# VRAM_SIMM_TC524258BJ_v1_0_Sch_EasyEDA.net
KiCad netlist of a schematic drawn in EasyEDA
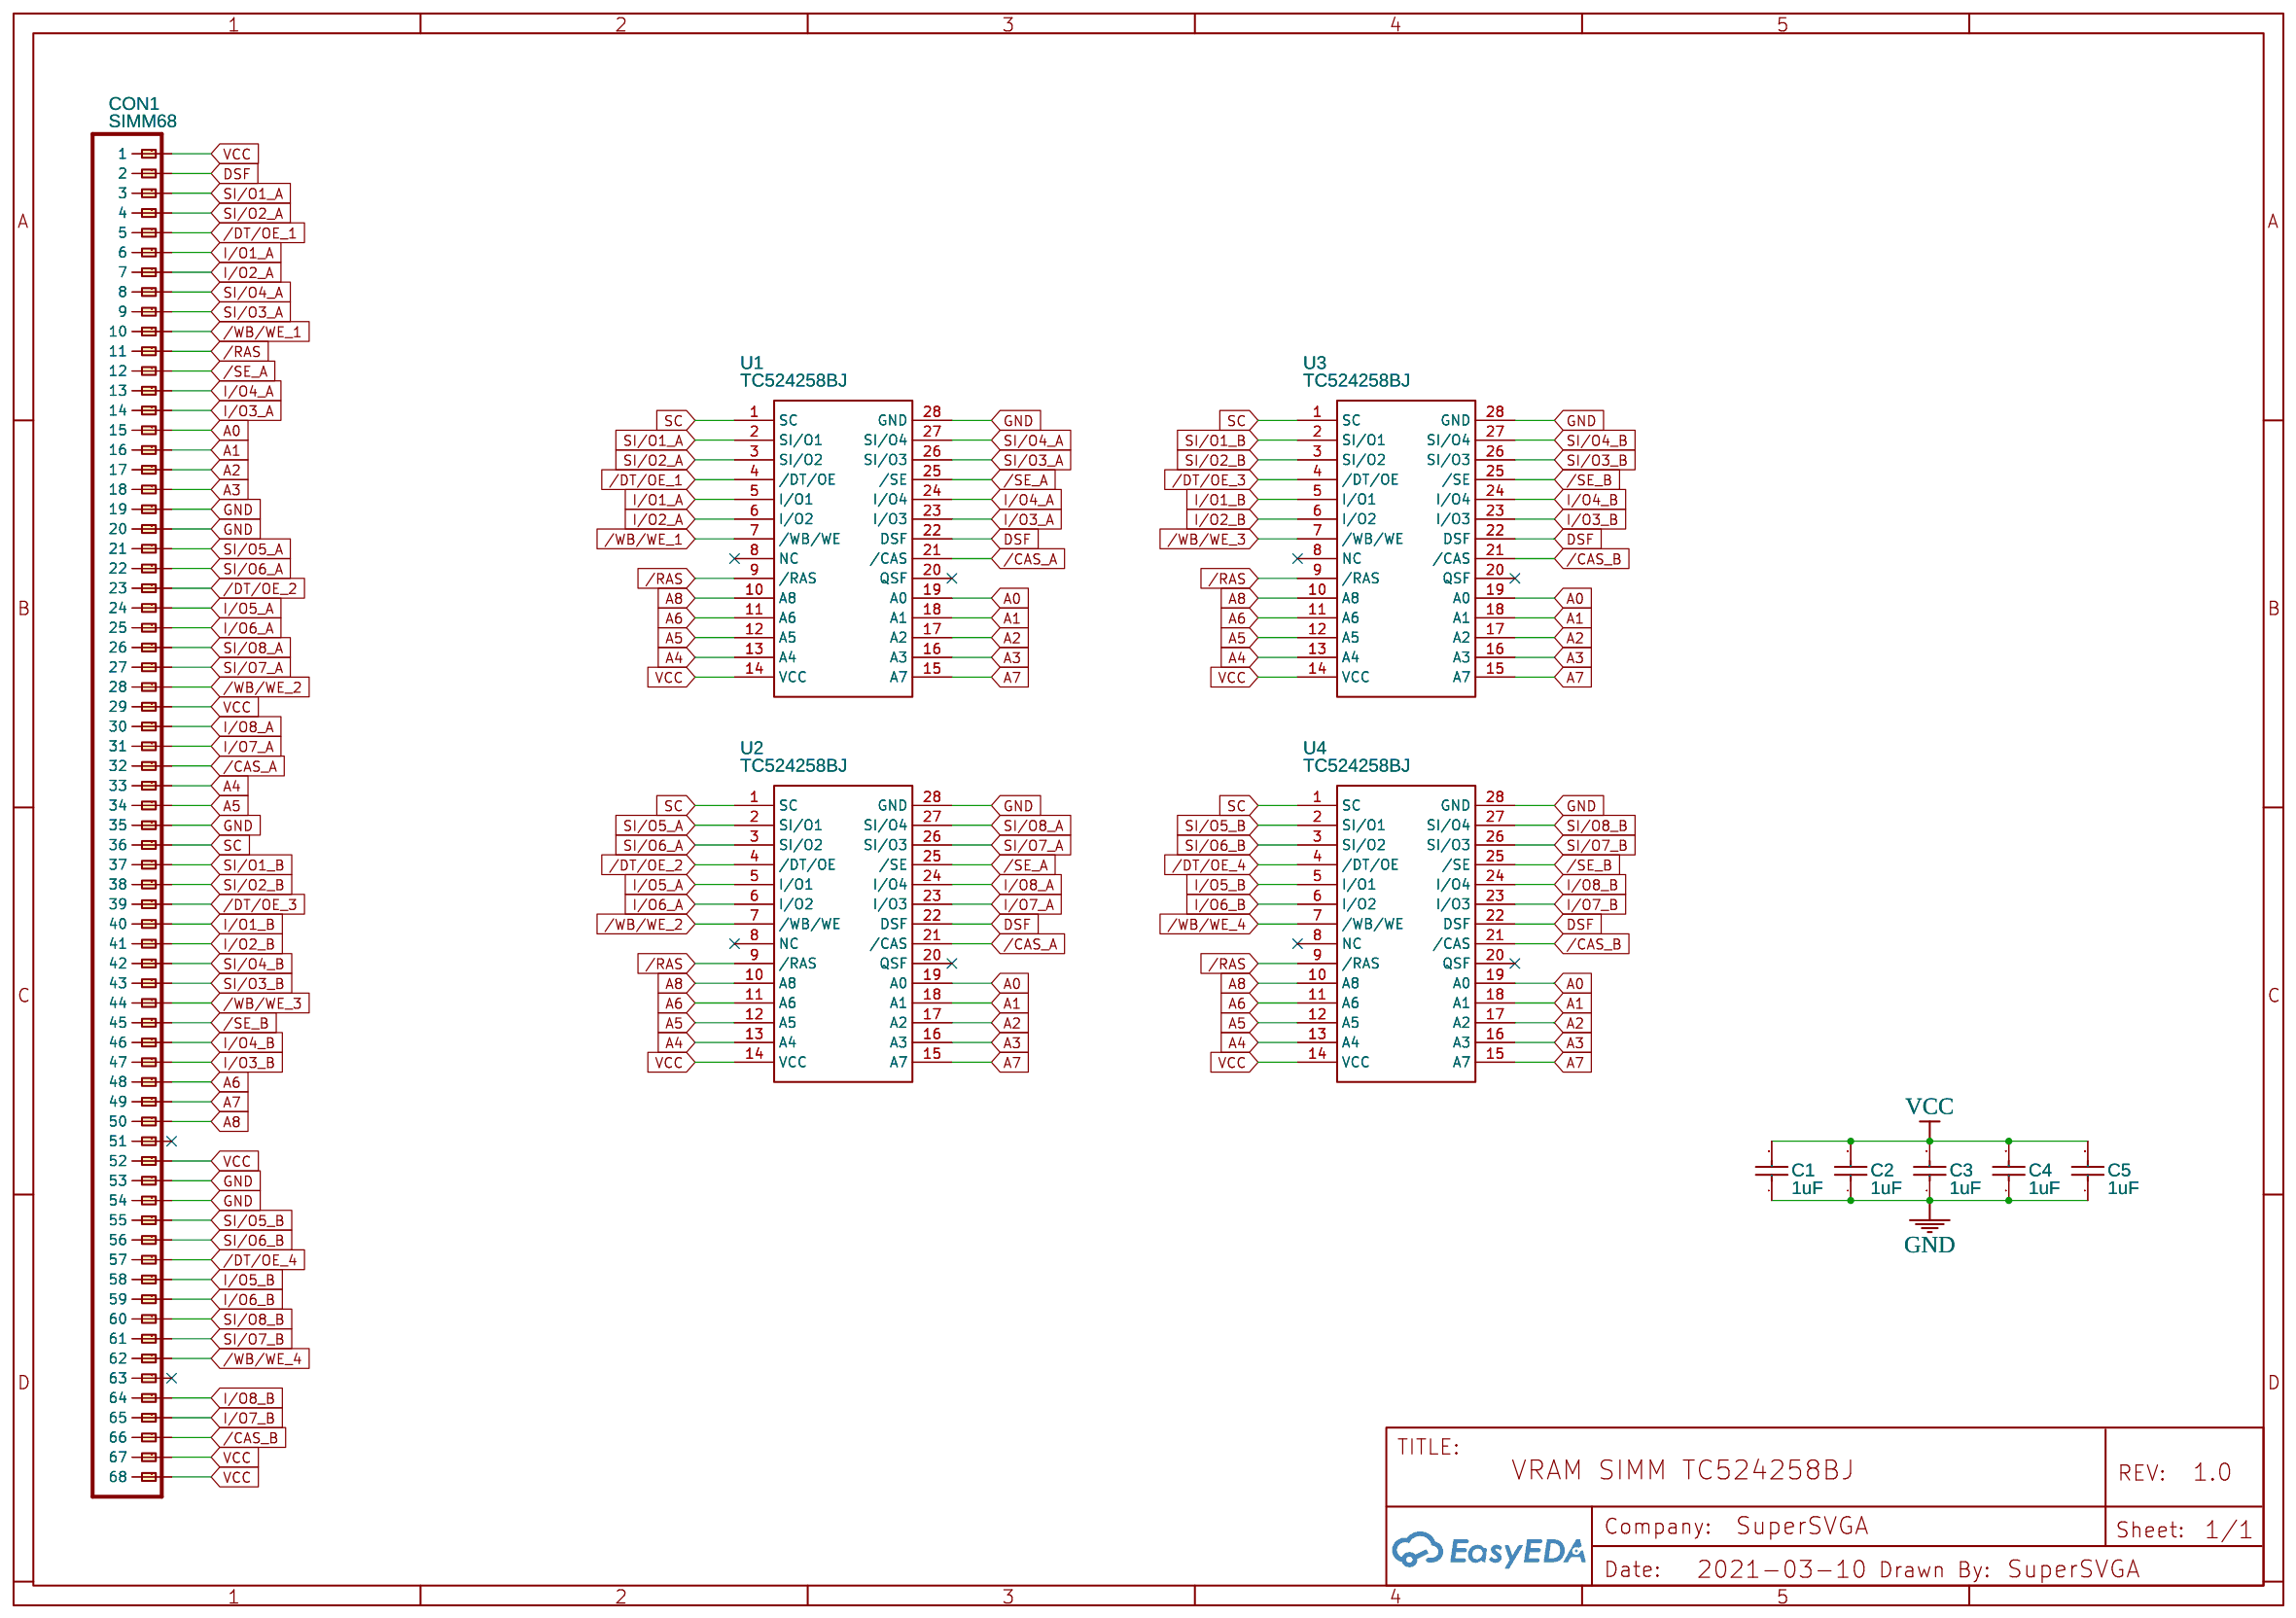
[diagram p0: schematic sheet]

(export (version "E")
  (design (tool "Eeschema 10.0.6"))
  (components
    (comp (ref "C1")
      (value "1uF")
      (fields
        (field (name "BOM_Manufacturer Part") "CL10A105KP8NNNC")
        (field (name "BOM_Supplier Part") "C26413")
      )
      (libsource (lib "") (part "CL10A105KP8NNNC"))
    )
    (comp (ref "C2")
      (value "1uF")
      (fields
        (field (name "BOM_Manufacturer Part") "CL10A105KP8NNNC")
        (field (name "BOM_Supplier Part") "C26413")
      )
      (libsource (lib "") (part "CL10A105KP8NNNC"))
    )
    (comp (ref "C3")
      (value "1uF")
      (fields
        (field (name "BOM_Manufacturer Part") "CL10A105KP8NNNC")
        (field (name "BOM_Supplier Part") "C26413")
      )
      (libsource (lib "") (part "CL10A105KP8NNNC"))
    )
    (comp (ref "C4")
      (value "1uF")
      (fields
        (field (name "BOM_Manufacturer Part") "CL10A105KP8NNNC")
        (field (name "BOM_Supplier Part") "C26413")
      )
      (libsource (lib "") (part "CL10A105KP8NNNC"))
    )
    (comp (ref "C5")
      (value "1uF")
      (fields
        (field (name "BOM_Manufacturer Part") "CL10A105KP8NNNC")
        (field (name "BOM_Supplier Part") "C26413")
      )
      (libsource (lib "") (part "CL10A105KP8NNNC"))
    )
    (comp (ref "CON1") (value "SIMM68") (libsource (lib "") (part "SIMM68")))
    (comp (ref "U1") (value "TC524258BJ") (libsource (lib "") (part "TC524258BJ")))
    (comp (ref "U2") (value "TC524258BJ") (libsource (lib "") (part "TC524258BJ")))
    (comp (ref "U3") (value "TC524258BJ") (libsource (lib "") (part "TC524258BJ")))
    (comp (ref "U4") (value "TC524258BJ") (libsource (lib "") (part "TC524258BJ")))
  )
  (nets
    (net (code "1") (name "A0") (class "Default")
      (node (ref "CON1") (pin "15") (pinfunction "15_15") (pintype "unspecified"))
      (node (ref "U1") (pin "19") (pinfunction "A0_19") (pintype "unspecified"))
      (node (ref "U2") (pin "19") (pinfunction "A0_19") (pintype "unspecified"))
      (node (ref "U3") (pin "19") (pinfunction "A0_19") (pintype "unspecified"))
      (node (ref "U4") (pin "19") (pinfunction "A0_19") (pintype "unspecified"))
    )
    (net (code "2") (name "A1") (class "Default")
      (node (ref "CON1") (pin "16") (pinfunction "16_16") (pintype "unspecified"))
      (node (ref "U1") (pin "18") (pinfunction "A1_18") (pintype "unspecified"))
      (node (ref "U2") (pin "18") (pinfunction "A1_18") (pintype "unspecified"))
      (node (ref "U3") (pin "18") (pinfunction "A1_18") (pintype "unspecified"))
      (node (ref "U4") (pin "18") (pinfunction "A1_18") (pintype "unspecified"))
    )
    (net (code "3") (name "A2") (class "Default")
      (node (ref "CON1") (pin "17") (pinfunction "17_17") (pintype "unspecified"))
      (node (ref "U1") (pin "17") (pinfunction "A2_17") (pintype "unspecified"))
      (node (ref "U2") (pin "17") (pinfunction "A2_17") (pintype "unspecified"))
      (node (ref "U3") (pin "17") (pinfunction "A2_17") (pintype "unspecified"))
      (node (ref "U4") (pin "17") (pinfunction "A2_17") (pintype "unspecified"))
    )
    (net (code "4") (name "A3") (class "Default")
      (node (ref "CON1") (pin "18") (pinfunction "18_18") (pintype "unspecified"))
      (node (ref "U1") (pin "16") (pinfunction "A3_16") (pintype "unspecified"))
      (node (ref "U2") (pin "16") (pinfunction "A3_16") (pintype "unspecified"))
      (node (ref "U3") (pin "16") (pinfunction "A3_16") (pintype "unspecified"))
      (node (ref "U4") (pin "16") (pinfunction "A3_16") (pintype "unspecified"))
    )
    (net (code "5") (name "A4") (class "Default")
      (node (ref "CON1") (pin "33") (pinfunction "33_33") (pintype "unspecified"))
      (node (ref "U1") (pin "13") (pinfunction "A4_13") (pintype "unspecified"))
      (node (ref "U2") (pin "13") (pinfunction "A4_13") (pintype "unspecified"))
      (node (ref "U3") (pin "13") (pinfunction "A4_13") (pintype "unspecified"))
      (node (ref "U4") (pin "13") (pinfunction "A4_13") (pintype "unspecified"))
    )
    (net (code "6") (name "A5") (class "Default")
      (node (ref "CON1") (pin "34") (pinfunction "34_34") (pintype "unspecified"))
      (node (ref "U1") (pin "12") (pinfunction "A5_12") (pintype "unspecified"))
      (node (ref "U2") (pin "12") (pinfunction "A5_12") (pintype "unspecified"))
      (node (ref "U3") (pin "12") (pinfunction "A5_12") (pintype "unspecified"))
      (node (ref "U4") (pin "12") (pinfunction "A5_12") (pintype "unspecified"))
    )
    (net (code "7") (name "A6") (class "Default")
      (node (ref "CON1") (pin "48") (pinfunction "48_48") (pintype "unspecified"))
      (node (ref "U1") (pin "11") (pinfunction "A6_11") (pintype "unspecified"))
      (node (ref "U2") (pin "11") (pinfunction "A6_11") (pintype "unspecified"))
      (node (ref "U3") (pin "11") (pinfunction "A6_11") (pintype "unspecified"))
      (node (ref "U4") (pin "11") (pinfunction "A6_11") (pintype "unspecified"))
    )
    (net (code "8") (name "A7") (class "Default")
      (node (ref "CON1") (pin "49") (pinfunction "49_49") (pintype "unspecified"))
      (node (ref "U1") (pin "15") (pinfunction "A7_15") (pintype "unspecified"))
      (node (ref "U2") (pin "15") (pinfunction "A7_15") (pintype "unspecified"))
      (node (ref "U3") (pin "15") (pinfunction "A7_15") (pintype "unspecified"))
      (node (ref "U4") (pin "15") (pinfunction "A7_15") (pintype "unspecified"))
    )
    (net (code "9") (name "A8") (class "Default")
      (node (ref "CON1") (pin "50") (pinfunction "50_50") (pintype "unspecified"))
      (node (ref "U1") (pin "10") (pinfunction "A8_10") (pintype "unspecified"))
      (node (ref "U2") (pin "10") (pinfunction "A8_10") (pintype "unspecified"))
      (node (ref "U3") (pin "10") (pinfunction "A8_10") (pintype "unspecified"))
      (node (ref "U4") (pin "10") (pinfunction "A8_10") (pintype "unspecified"))
    )
    (net (code "10") (name "DSF") (class "Default")
      (node (ref "CON1") (pin "2") (pinfunction "2_2") (pintype "unspecified"))
      (node (ref "U1") (pin "22") (pinfunction "DSF_22") (pintype "unspecified"))
      (node (ref "U2") (pin "22") (pinfunction "DSF_22") (pintype "unspecified"))
      (node (ref "U3") (pin "22") (pinfunction "DSF_22") (pintype "unspecified"))
      (node (ref "U4") (pin "22") (pinfunction "DSF_22") (pintype "unspecified"))
    )
    (net (code "11") (name "GND") (class "Default")
      (node (ref "C1") (pin "1") (pinfunction "1_1") (pintype "input"))
      (node (ref "C2") (pin "1") (pinfunction "1_1") (pintype "input"))
      (node (ref "C3") (pin "1") (pinfunction "1_1") (pintype "input"))
      (node (ref "C4") (pin "1") (pinfunction "1_1") (pintype "input"))
      (node (ref "C5") (pin "1") (pinfunction "1_1") (pintype "input"))
      (node (ref "CON1") (pin "19") (pinfunction "19_19") (pintype "unspecified"))
      (node (ref "CON1") (pin "20") (pinfunction "20_20") (pintype "unspecified"))
      (node (ref "CON1") (pin "35") (pinfunction "35_35") (pintype "unspecified"))
      (node (ref "CON1") (pin "53") (pinfunction "53_53") (pintype "unspecified"))
      (node (ref "CON1") (pin "54") (pinfunction "54_54") (pintype "unspecified"))
      (node (ref "U1") (pin "28") (pinfunction "GND_28") (pintype "passive"))
      (node (ref "U2") (pin "28") (pinfunction "GND_28") (pintype "passive"))
      (node (ref "U3") (pin "28") (pinfunction "GND_28") (pintype "passive"))
      (node (ref "U4") (pin "28") (pinfunction "GND_28") (pintype "passive"))
    )
    (net (code "12") (name "I{slash}O1_A") (class "Default")
      (node (ref "CON1") (pin "6") (pinfunction "6_6") (pintype "unspecified"))
      (node (ref "U1") (pin "5") (pinfunction "I/O1_5") (pintype "unspecified"))
    )
    (net (code "13") (name "I{slash}O1_B") (class "Default")
      (node (ref "CON1") (pin "40") (pinfunction "40_40") (pintype "unspecified"))
      (node (ref "U3") (pin "5") (pinfunction "I/O1_5") (pintype "unspecified"))
    )
    (net (code "14") (name "I{slash}O2_A") (class "Default")
      (node (ref "CON1") (pin "7") (pinfunction "7_7") (pintype "unspecified"))
      (node (ref "U1") (pin "6") (pinfunction "I/O2_6") (pintype "unspecified"))
    )
    (net (code "15") (name "I{slash}O2_B") (class "Default")
      (node (ref "CON1") (pin "41") (pinfunction "41_41") (pintype "unspecified"))
      (node (ref "U3") (pin "6") (pinfunction "I/O2_6") (pintype "unspecified"))
    )
    (net (code "16") (name "I{slash}O3_A") (class "Default")
      (node (ref "CON1") (pin "14") (pinfunction "14_14") (pintype "unspecified"))
      (node (ref "U1") (pin "23") (pinfunction "I/O3_23") (pintype "unspecified"))
    )
    (net (code "17") (name "I{slash}O3_B") (class "Default")
      (node (ref "CON1") (pin "47") (pinfunction "47_47") (pintype "unspecified"))
      (node (ref "U3") (pin "23") (pinfunction "I/O3_23") (pintype "unspecified"))
    )
    (net (code "18") (name "I{slash}O4_A") (class "Default")
      (node (ref "CON1") (pin "13") (pinfunction "13_13") (pintype "unspecified"))
      (node (ref "U1") (pin "24") (pinfunction "I/O4_24") (pintype "unspecified"))
    )
    (net (code "19") (name "I{slash}O4_B") (class "Default")
      (node (ref "CON1") (pin "46") (pinfunction "46_46") (pintype "unspecified"))
      (node (ref "U3") (pin "24") (pinfunction "I/O4_24") (pintype "unspecified"))
    )
    (net (code "20") (name "I{slash}O5_A") (class "Default")
      (node (ref "CON1") (pin "24") (pinfunction "24_24") (pintype "unspecified"))
      (node (ref "U2") (pin "5") (pinfunction "I/O1_5") (pintype "unspecified"))
    )
    (net (code "21") (name "I{slash}O5_B") (class "Default")
      (node (ref "CON1") (pin "58") (pinfunction "58_58") (pintype "unspecified"))
      (node (ref "U4") (pin "5") (pinfunction "I/O1_5") (pintype "unspecified"))
    )
    (net (code "22") (name "I{slash}O6_A") (class "Default")
      (node (ref "CON1") (pin "25") (pinfunction "25_25") (pintype "unspecified"))
      (node (ref "U2") (pin "6") (pinfunction "I/O2_6") (pintype "unspecified"))
    )
    (net (code "23") (name "I{slash}O6_B") (class "Default")
      (node (ref "CON1") (pin "59") (pinfunction "59_59") (pintype "unspecified"))
      (node (ref "U4") (pin "6") (pinfunction "I/O2_6") (pintype "unspecified"))
    )
    (net (code "24") (name "I{slash}O7_A") (class "Default")
      (node (ref "CON1") (pin "31") (pinfunction "31_31") (pintype "unspecified"))
      (node (ref "U2") (pin "23") (pinfunction "I/O3_23") (pintype "unspecified"))
    )
    (net (code "25") (name "I{slash}O7_B") (class "Default")
      (node (ref "CON1") (pin "65") (pinfunction "65_65") (pintype "unspecified"))
      (node (ref "U4") (pin "23") (pinfunction "I/O3_23") (pintype "unspecified"))
    )
    (net (code "26") (name "I{slash}O8_A") (class "Default")
      (node (ref "CON1") (pin "30") (pinfunction "30_30") (pintype "unspecified"))
      (node (ref "U2") (pin "24") (pinfunction "I/O4_24") (pintype "unspecified"))
    )
    (net (code "27") (name "I{slash}O8_B") (class "Default")
      (node (ref "CON1") (pin "64") (pinfunction "64_64") (pintype "unspecified"))
      (node (ref "U4") (pin "24") (pinfunction "I/O4_24") (pintype "unspecified"))
    )
    (net (code "28") (name "SC") (class "Default")
      (node (ref "CON1") (pin "36") (pinfunction "36_36") (pintype "unspecified"))
      (node (ref "U1") (pin "1") (pinfunction "SC_1") (pintype "unspecified"))
      (node (ref "U2") (pin "1") (pinfunction "SC_1") (pintype "unspecified"))
      (node (ref "U3") (pin "1") (pinfunction "SC_1") (pintype "unspecified"))
      (node (ref "U4") (pin "1") (pinfunction "SC_1") (pintype "unspecified"))
    )
    (net (code "29") (name "SI{slash}O1_A") (class "Default")
      (node (ref "CON1") (pin "3") (pinfunction "3_3") (pintype "unspecified"))
      (node (ref "U1") (pin "2") (pinfunction "SI/O1_2") (pintype "unspecified"))
    )
    (net (code "30") (name "SI{slash}O1_B") (class "Default")
      (node (ref "CON1") (pin "37") (pinfunction "37_37") (pintype "unspecified"))
      (node (ref "U3") (pin "2") (pinfunction "SI/O1_2") (pintype "unspecified"))
    )
    (net (code "31") (name "SI{slash}O2_A") (class "Default")
      (node (ref "CON1") (pin "4") (pinfunction "4_4") (pintype "unspecified"))
      (node (ref "U1") (pin "3") (pinfunction "SI/O2_3") (pintype "unspecified"))
    )
    (net (code "32") (name "SI{slash}O2_B") (class "Default")
      (node (ref "CON1") (pin "38") (pinfunction "38_38") (pintype "unspecified"))
      (node (ref "U3") (pin "3") (pinfunction "SI/O2_3") (pintype "unspecified"))
    )
    (net (code "33") (name "SI{slash}O3_A") (class "Default")
      (node (ref "CON1") (pin "9") (pinfunction "9_9") (pintype "unspecified"))
      (node (ref "U1") (pin "26") (pinfunction "SI/O3_26") (pintype "unspecified"))
    )
    (net (code "34") (name "SI{slash}O3_B") (class "Default")
      (node (ref "CON1") (pin "43") (pinfunction "43_43") (pintype "unspecified"))
      (node (ref "U3") (pin "26") (pinfunction "SI/O3_26") (pintype "unspecified"))
    )
    (net (code "35") (name "SI{slash}O4_A") (class "Default")
      (node (ref "CON1") (pin "8") (pinfunction "8_8") (pintype "unspecified"))
      (node (ref "U1") (pin "27") (pinfunction "SI/O4_27") (pintype "unspecified"))
    )
    (net (code "36") (name "SI{slash}O4_B") (class "Default")
      (node (ref "CON1") (pin "42") (pinfunction "42_42") (pintype "unspecified"))
      (node (ref "U3") (pin "27") (pinfunction "SI/O4_27") (pintype "unspecified"))
    )
    (net (code "37") (name "SI{slash}O5_A") (class "Default")
      (node (ref "CON1") (pin "21") (pinfunction "21_21") (pintype "unspecified"))
      (node (ref "U2") (pin "2") (pinfunction "SI/O1_2") (pintype "unspecified"))
    )
    (net (code "38") (name "SI{slash}O5_B") (class "Default")
      (node (ref "CON1") (pin "55") (pinfunction "55_55") (pintype "unspecified"))
      (node (ref "U4") (pin "2") (pinfunction "SI/O1_2") (pintype "unspecified"))
    )
    (net (code "39") (name "SI{slash}O6_A") (class "Default")
      (node (ref "CON1") (pin "22") (pinfunction "22_22") (pintype "unspecified"))
      (node (ref "U2") (pin "3") (pinfunction "SI/O2_3") (pintype "unspecified"))
    )
    (net (code "40") (name "SI{slash}O6_B") (class "Default")
      (node (ref "CON1") (pin "56") (pinfunction "56_56") (pintype "unspecified"))
      (node (ref "U4") (pin "3") (pinfunction "SI/O2_3") (pintype "unspecified"))
    )
    (net (code "41") (name "SI{slash}O7_A") (class "Default")
      (node (ref "CON1") (pin "27") (pinfunction "27_27") (pintype "unspecified"))
      (node (ref "U2") (pin "26") (pinfunction "SI/O3_26") (pintype "unspecified"))
    )
    (net (code "42") (name "SI{slash}O7_B") (class "Default")
      (node (ref "CON1") (pin "61") (pinfunction "61_61") (pintype "unspecified"))
      (node (ref "U4") (pin "26") (pinfunction "SI/O3_26") (pintype "unspecified"))
    )
    (net (code "43") (name "SI{slash}O8_A") (class "Default")
      (node (ref "CON1") (pin "26") (pinfunction "26_26") (pintype "unspecified"))
      (node (ref "U2") (pin "27") (pinfunction "SI/O4_27") (pintype "unspecified"))
    )
    (net (code "44") (name "SI{slash}O8_B") (class "Default")
      (node (ref "CON1") (pin "60") (pinfunction "60_60") (pintype "unspecified"))
      (node (ref "U4") (pin "27") (pinfunction "SI/O4_27") (pintype "unspecified"))
    )
    (net (code "45") (name "VCC") (class "Default")
      (node (ref "C1") (pin "2") (pinfunction "2_2") (pintype "input"))
      (node (ref "C2") (pin "2") (pinfunction "2_2") (pintype "input"))
      (node (ref "C3") (pin "2") (pinfunction "2_2") (pintype "input"))
      (node (ref "C4") (pin "2") (pinfunction "2_2") (pintype "input"))
      (node (ref "C5") (pin "2") (pinfunction "2_2") (pintype "input"))
      (node (ref "CON1") (pin "1") (pinfunction "1_1") (pintype "unspecified"))
      (node (ref "CON1") (pin "29") (pinfunction "29_29") (pintype "unspecified"))
      (node (ref "CON1") (pin "52") (pinfunction "52_52") (pintype "unspecified"))
      (node (ref "CON1") (pin "67") (pinfunction "67_67") (pintype "unspecified"))
      (node (ref "CON1") (pin "68") (pinfunction "68_68") (pintype "unspecified"))
      (node (ref "U1") (pin "14") (pinfunction "VCC_14") (pintype "unspecified"))
      (node (ref "U2") (pin "14") (pinfunction "VCC_14") (pintype "unspecified"))
      (node (ref "U3") (pin "14") (pinfunction "VCC_14") (pintype "unspecified"))
      (node (ref "U4") (pin "14") (pinfunction "VCC_14") (pintype "unspecified"))
    )
    (net (code "46") (name "unconnected-(CON1-Pad51)") (class "Default")
      (node (ref "CON1") (pin "51") (pinfunction "51_51") (pintype "unspecified+no_connect"))
    )
    (net (code "47") (name "unconnected-(CON1-Pad63)") (class "Default")
      (node (ref "CON1") (pin "63") (pinfunction "63_63") (pintype "unspecified+no_connect"))
    )
    (net (code "48") (name "unconnected-(U1-NC-Pad8)") (class "Default")
      (node (ref "U1") (pin "8") (pinfunction "NC_8") (pintype "unspecified+no_connect"))
    )
    (net (code "49") (name "unconnected-(U1-QSF-Pad20)") (class "Default")
      (node (ref "U1") (pin "20") (pinfunction "QSF_20") (pintype "unspecified+no_connect"))
    )
    (net (code "50") (name "unconnected-(U2-NC-Pad8)") (class "Default")
      (node (ref "U2") (pin "8") (pinfunction "NC_8") (pintype "unspecified+no_connect"))
    )
    (net (code "51") (name "unconnected-(U2-QSF-Pad20)") (class "Default")
      (node (ref "U2") (pin "20") (pinfunction "QSF_20") (pintype "unspecified+no_connect"))
    )
    (net (code "52") (name "unconnected-(U3-NC-Pad8)") (class "Default")
      (node (ref "U3") (pin "8") (pinfunction "NC_8") (pintype "unspecified+no_connect"))
    )
    (net (code "53") (name "unconnected-(U3-QSF-Pad20)") (class "Default")
      (node (ref "U3") (pin "20") (pinfunction "QSF_20") (pintype "unspecified+no_connect"))
    )
    (net (code "54") (name "unconnected-(U4-NC-Pad8)") (class "Default")
      (node (ref "U4") (pin "8") (pinfunction "NC_8") (pintype "unspecified+no_connect"))
    )
    (net (code "55") (name "unconnected-(U4-QSF-Pad20)") (class "Default")
      (node (ref "U4") (pin "20") (pinfunction "QSF_20") (pintype "unspecified+no_connect"))
    )
    (net (code "56") (name "{slash}CAS_A") (class "Default")
      (node (ref "CON1") (pin "32") (pinfunction "32_32") (pintype "unspecified"))
      (node (ref "U1") (pin "21") (pinfunction "/CAS_21") (pintype "unspecified"))
      (node (ref "U2") (pin "21") (pinfunction "/CAS_21") (pintype "unspecified"))
    )
    (net (code "57") (name "{slash}CAS_B") (class "Default")
      (node (ref "CON1") (pin "66") (pinfunction "66_66") (pintype "unspecified"))
      (node (ref "U3") (pin "21") (pinfunction "/CAS_21") (pintype "unspecified"))
      (node (ref "U4") (pin "21") (pinfunction "/CAS_21") (pintype "unspecified"))
    )
    (net (code "58") (name "{slash}DT{slash}OE_1") (class "Default")
      (node (ref "CON1") (pin "5") (pinfunction "5_5") (pintype "unspecified"))
      (node (ref "U1") (pin "4") (pinfunction "/DT/OE_4") (pintype "unspecified"))
    )
    (net (code "59") (name "{slash}DT{slash}OE_2") (class "Default")
      (node (ref "CON1") (pin "23") (pinfunction "23_23") (pintype "unspecified"))
      (node (ref "U2") (pin "4") (pinfunction "/DT/OE_4") (pintype "unspecified"))
    )
    (net (code "60") (name "{slash}DT{slash}OE_3") (class "Default")
      (node (ref "CON1") (pin "39") (pinfunction "39_39") (pintype "unspecified"))
      (node (ref "U3") (pin "4") (pinfunction "/DT/OE_4") (pintype "unspecified"))
    )
    (net (code "61") (name "{slash}DT{slash}OE_4") (class "Default")
      (node (ref "CON1") (pin "57") (pinfunction "57_57") (pintype "unspecified"))
      (node (ref "U4") (pin "4") (pinfunction "/DT/OE_4") (pintype "unspecified"))
    )
    (net (code "62") (name "{slash}RAS") (class "Default")
      (node (ref "CON1") (pin "11") (pinfunction "11_11") (pintype "unspecified"))
      (node (ref "U1") (pin "9") (pinfunction "/RAS_9") (pintype "unspecified"))
      (node (ref "U2") (pin "9") (pinfunction "/RAS_9") (pintype "unspecified"))
      (node (ref "U3") (pin "9") (pinfunction "/RAS_9") (pintype "unspecified"))
      (node (ref "U4") (pin "9") (pinfunction "/RAS_9") (pintype "unspecified"))
    )
    (net (code "63") (name "{slash}SE_A") (class "Default")
      (node (ref "CON1") (pin "12") (pinfunction "12_12") (pintype "unspecified"))
      (node (ref "U1") (pin "25") (pinfunction "/SE_25") (pintype "unspecified"))
      (node (ref "U2") (pin "25") (pinfunction "/SE_25") (pintype "unspecified"))
    )
    (net (code "64") (name "{slash}SE_B") (class "Default")
      (node (ref "CON1") (pin "45") (pinfunction "45_45") (pintype "unspecified"))
      (node (ref "U3") (pin "25") (pinfunction "/SE_25") (pintype "unspecified"))
      (node (ref "U4") (pin "25") (pinfunction "/SE_25") (pintype "unspecified"))
    )
    (net (code "65") (name "{slash}WB{slash}WE_1") (class "Default")
      (node (ref "CON1") (pin "10") (pinfunction "10_10") (pintype "unspecified"))
      (node (ref "U1") (pin "7") (pinfunction "/WB/WE_7") (pintype "unspecified"))
    )
    (net (code "66") (name "{slash}WB{slash}WE_2") (class "Default")
      (node (ref "CON1") (pin "28") (pinfunction "28_28") (pintype "unspecified"))
      (node (ref "U2") (pin "7") (pinfunction "/WB/WE_7") (pintype "unspecified"))
    )
    (net (code "67") (name "{slash}WB{slash}WE_3") (class "Default")
      (node (ref "CON1") (pin "44") (pinfunction "44_44") (pintype "unspecified"))
      (node (ref "U3") (pin "7") (pinfunction "/WB/WE_7") (pintype "unspecified"))
    )
    (net (code "68") (name "{slash}WB{slash}WE_4") (class "Default")
      (node (ref "CON1") (pin "62") (pinfunction "62_62") (pintype "unspecified"))
      (node (ref "U4") (pin "7") (pinfunction "/WB/WE_7") (pintype "unspecified"))
    )
  )
)
